# LB_BIT_2IN_1OUT-XL-v03_1_1x.net
KiCad netlist of a schematic drawn in EAGLE
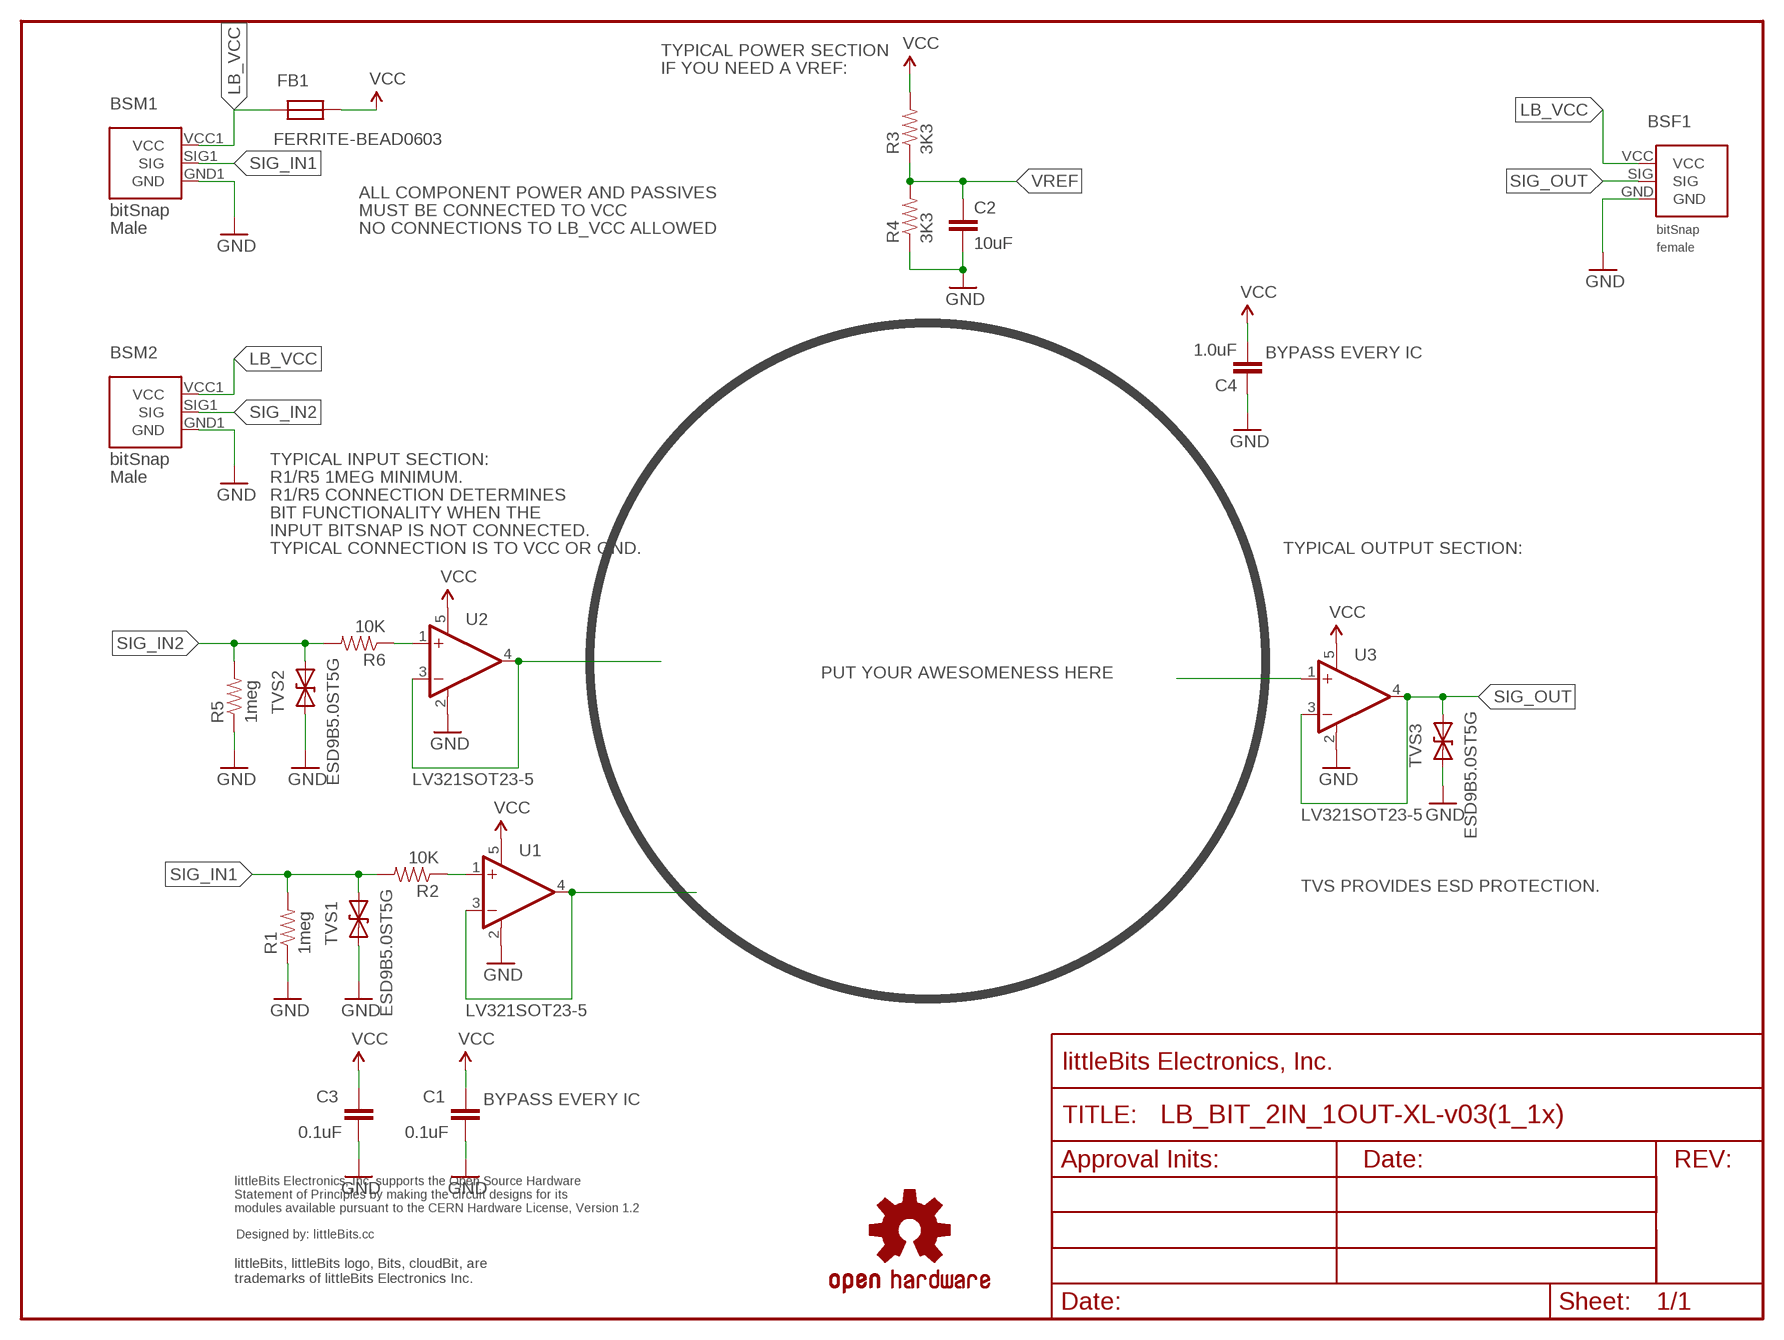
[diagram p0: schematic, sheet 1]

(export (version "E")
  (design (tool "Eeschema 10.0.6"))
  (components
    (comp (ref "BSF1")
      (value "BITSNAP_V03_FEMALE")
      (footprint "eagle-import:BITSNAP_V03_FEMALE")
      (libsource (lib "eagle-import") (part "BITSNAP_V03_FEMALE"))
    )
    (comp (ref "BSM1")
      (value "BITSNAP_V03_MALE")
      (footprint "eagle-import:BITSNAP_V03_MALE")
      (libsource (lib "eagle-import") (part "BITSNAP_V03_MALE"))
    )
    (comp (ref "BSM2")
      (value "BITSNAP_V03_MALE")
      (footprint "eagle-import:BITSNAP_V03_MALE")
      (libsource (lib "eagle-import") (part "BITSNAP_V03_MALE"))
    )
    (comp (ref "C1")
      (value "0.1uF")
      (footprint "eagle-import:CAP-0603")
      (libsource (lib "eagle-import") (part "CAPCAP-0603"))
    )
    (comp (ref "C2")
      (value "10uF")
      (footprint "eagle-import:CAP-0603")
      (libsource (lib "eagle-import") (part "CAPCAP-0603"))
    )
    (comp (ref "C3")
      (value "0.1uF")
      (footprint "eagle-import:CAP-0603")
      (libsource (lib "eagle-import") (part "CAPCAP-0603"))
    )
    (comp (ref "C4")
      (value "1.0uF")
      (footprint "eagle-import:CAP-0603")
      (libsource (lib "eagle-import") (part "CAPCAP-0603"))
    )
    (comp (ref "FB1")
      (value "FERRITE-BEAD0603")
      (footprint "eagle-import:R0603")
      (libsource (lib "eagle-import") (part "FERRITE-BEAD0603"))
    )
    (comp (ref "FRAME1")
      (value "FRAME-LETTER")
      (footprint "eagle-import:FABDWG01-OHW")
      (libsource (lib "eagle-import") (part "FRAME-LETTER"))
    )
    (comp (ref "R1")
      (value "1meg")
      (footprint "eagle-import:RES-0603")
      (libsource (lib "eagle-import") (part "RESISTOR0603"))
    )
    (comp (ref "R2")
      (value "10K")
      (footprint "eagle-import:RES-0603")
      (libsource (lib "eagle-import") (part "RESISTOR0603"))
    )
    (comp (ref "R3")
      (value "3K3")
      (footprint "eagle-import:RES-0603")
      (libsource (lib "eagle-import") (part "RESISTOR0603"))
    )
    (comp (ref "R4")
      (value "3K3")
      (footprint "eagle-import:RES-0603")
      (libsource (lib "eagle-import") (part "RESISTOR0603"))
    )
    (comp (ref "R5")
      (value "1meg")
      (footprint "eagle-import:RES-0603")
      (libsource (lib "eagle-import") (part "RESISTOR0603"))
    )
    (comp (ref "R6")
      (value "10K")
      (footprint "eagle-import:RES-0603")
      (libsource (lib "eagle-import") (part "RESISTOR0603"))
    )
    (comp (ref "TVS1")
      (value "ESD9B5.0ST5G")
      (footprint "eagle-import:SOD-923")
      (libsource (lib "eagle-import") (part "DIODE-TVSSOD-923"))
    )
    (comp (ref "TVS2")
      (value "ESD9B5.0ST5G")
      (footprint "eagle-import:SOD-923")
      (libsource (lib "eagle-import") (part "DIODE-TVSSOD-923"))
    )
    (comp (ref "TVS3")
      (value "ESD9B5.0ST5G")
      (footprint "eagle-import:SOD-923")
      (libsource (lib "eagle-import") (part "DIODE-TVSSOD-923"))
    )
    (comp (ref "U$1")
      (value "OSHW-LOGOL")
      (footprint "eagle-import:OSHW-LOGO-L")
      (libsource (lib "eagle-import") (part "OSHW-LOGOL"))
    )
    (comp (ref "U$3")
      (value "OSHWCREDIT")
      (footprint "eagle-import:OSHWCREDIT")
      (libsource (lib "eagle-import") (part "OSHWCREDIT"))
    )
    (comp (ref "U1")
      (value "LV321SOT23-5")
      (footprint "eagle-import:SOT23-5")
      (libsource (lib "eagle-import") (part "LV321SOT23-5"))
    )
    (comp (ref "U2")
      (value "LV321SOT23-5")
      (footprint "eagle-import:SOT23-5")
      (libsource (lib "eagle-import") (part "LV321SOT23-5"))
    )
    (comp (ref "U3")
      (value "LV321SOT23-5")
      (footprint "eagle-import:SOT23-5")
      (libsource (lib "eagle-import") (part "LV321SOT23-5"))
    )
  )
  (nets
    (net (code "1") (name "GND") (class "Default")
      (node (ref "BSF1") (pin "GND") (pinfunction "GND_GND") (pintype "bidirectional"))
      (node (ref "BSM1") (pin "GND1") (pinfunction "GND_GND1") (pintype "bidirectional"))
      (node (ref "BSM2") (pin "GND1") (pinfunction "GND_GND1") (pintype "bidirectional"))
      (node (ref "C1") (pin "2") (pinfunction "2_2") (pintype "passive"))
      (node (ref "C2") (pin "2") (pinfunction "2_2") (pintype "passive"))
      (node (ref "C3") (pin "2") (pinfunction "2_2") (pintype "passive"))
      (node (ref "C4") (pin "1") (pinfunction "1_1") (pintype "passive"))
      (node (ref "R1") (pin "1") (pinfunction "1_1") (pintype "passive"))
      (node (ref "R4") (pin "1") (pinfunction "1_1") (pintype "passive"))
      (node (ref "R5") (pin "1") (pinfunction "1_1") (pintype "passive"))
      (node (ref "TVS1") (pin "1") (pinfunction "A_1") (pintype "passive"))
      (node (ref "TVS2") (pin "1") (pinfunction "A_1") (pintype "passive"))
      (node (ref "TVS3") (pin "1") (pinfunction "A_1") (pintype "passive"))
      (node (ref "U1") (pin "2") (pinfunction "V-_2") (pintype "power_in"))
      (node (ref "U2") (pin "2") (pinfunction "V-_2") (pintype "power_in"))
      (node (ref "U3") (pin "2") (pinfunction "V-_2") (pintype "power_in"))
    )
    (net (code "2") (name "LB_VCC") (class "Default")
      (node (ref "BSF1") (pin "VCC") (pinfunction "VCC_VCC") (pintype "bidirectional"))
      (node (ref "BSM1") (pin "VCC1") (pinfunction "VCC_VCC1") (pintype "bidirectional"))
      (node (ref "BSM2") (pin "VCC1") (pinfunction "VCC_VCC1") (pintype "bidirectional"))
      (node (ref "FB1") (pin "2") (pinfunction "P$2_2") (pintype "bidirectional"))
    )
    (net (code "3") (name "Net-(U1-+IN)") (class "Default")
      (node (ref "R2") (pin "1") (pinfunction "1_1") (pintype "passive"))
      (node (ref "U1") (pin "1") (pinfunction "+IN_1") (pintype "input"))
    )
    (net (code "4") (name "Net-(U1--IN)") (class "Default")
      (node (ref "U1") (pin "3") (pinfunction "-IN_3") (pintype "input"))
      (node (ref "U1") (pin "4") (pinfunction "OUT_4") (pintype "output"))
    )
    (net (code "5") (name "Net-(U2-+IN)") (class "Default")
      (node (ref "R6") (pin "1") (pinfunction "1_1") (pintype "passive"))
      (node (ref "U2") (pin "1") (pinfunction "+IN_1") (pintype "input"))
    )
    (net (code "6") (name "Net-(U2--IN)") (class "Default")
      (node (ref "U2") (pin "3") (pinfunction "-IN_3") (pintype "input"))
      (node (ref "U2") (pin "4") (pinfunction "OUT_4") (pintype "output"))
    )
    (net (code "7") (name "SIG_IN1") (class "Default")
      (node (ref "BSM1") (pin "SIG1") (pinfunction "SIG_SIG1") (pintype "bidirectional"))
      (node (ref "R1") (pin "2") (pinfunction "2_2") (pintype "passive"))
      (node (ref "R2") (pin "2") (pinfunction "2_2") (pintype "passive"))
      (node (ref "TVS1") (pin "2") (pinfunction "C_2") (pintype "passive"))
    )
    (net (code "8") (name "SIG_IN2") (class "Default")
      (node (ref "BSM2") (pin "SIG1") (pinfunction "SIG_SIG1") (pintype "bidirectional"))
      (node (ref "R5") (pin "2") (pinfunction "2_2") (pintype "passive"))
      (node (ref "R6") (pin "2") (pinfunction "2_2") (pintype "passive"))
      (node (ref "TVS2") (pin "2") (pinfunction "C_2") (pintype "passive"))
    )
    (net (code "9") (name "SIG_OUT") (class "Default")
      (node (ref "BSF1") (pin "SIG") (pinfunction "SIG_SIG") (pintype "bidirectional"))
      (node (ref "TVS3") (pin "2") (pinfunction "C_2") (pintype "passive"))
      (node (ref "U3") (pin "3") (pinfunction "-IN_3") (pintype "input"))
      (node (ref "U3") (pin "4") (pinfunction "OUT_4") (pintype "output"))
    )
    (net (code "10") (name "VCC") (class "Default")
      (node (ref "C1") (pin "1") (pinfunction "1_1") (pintype "passive"))
      (node (ref "C3") (pin "1") (pinfunction "1_1") (pintype "passive"))
      (node (ref "C4") (pin "2") (pinfunction "2_2") (pintype "passive"))
      (node (ref "FB1") (pin "1") (pinfunction "P$1_1") (pintype "bidirectional"))
      (node (ref "R3") (pin "2") (pinfunction "2_2") (pintype "passive"))
      (node (ref "U1") (pin "5") (pinfunction "V+_5") (pintype "power_in"))
      (node (ref "U2") (pin "5") (pinfunction "V+_5") (pintype "power_in"))
      (node (ref "U3") (pin "5") (pinfunction "V+_5") (pintype "power_in"))
    )
    (net (code "11") (name "VREF") (class "Default")
      (node (ref "C2") (pin "1") (pinfunction "1_1") (pintype "passive"))
      (node (ref "R3") (pin "1") (pinfunction "1_1") (pintype "passive"))
      (node (ref "R4") (pin "2") (pinfunction "2_2") (pintype "passive"))
    )
    (net (code "12") (name "unconnected-(U3-+IN-Pad1)") (class "Default")
      (node (ref "U3") (pin "1") (pinfunction "+IN_1") (pintype "input"))
    )
  )
)
